# RelayDriver.net
KiCad netlist of a schematic drawn in Altium Designer
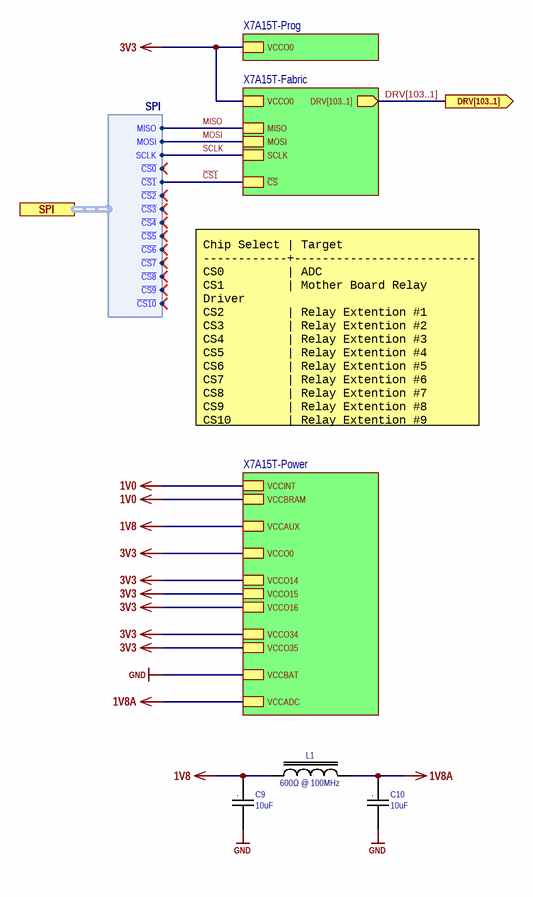
[diagram p0: RelayDriver.SchDoc]

(export (version "E")
  (design (tool "Eeschema 10.0.6"))
  (components
    (comp (ref "C9")
      (value "10uF")
      (footprint "C0805 Reflow")
      (description "CAP CER 10UF 10V X7R 0805")
      (fields
        (field (name "TOLERANCE") "±10%")
        (field (name "02. DISTRIBUTOR PART NUMBER") "1276-1764-6-ND")
        (field (name "13. CREATED DATE/NAME") "AUG2018/Hören")
      )
      (libsource (lib "chickenfood") (part "C"))
    )
    (comp (ref "C10")
      (value "10uF")
      (footprint "C0805 Reflow")
      (description "CAP CER 10UF 10V X7R 0805")
      (fields
        (field (name "TOLERANCE") "±10%")
        (field (name "02. DISTRIBUTOR PART NUMBER") "1276-1764-6-ND")
        (field (name "13. CREATED DATE/NAME") "AUG2018/Hören")
      )
      (libsource (lib "chickenfood") (part "C"))
    )
    (comp (ref "L1")
      (value "L")
      (footprint "FB0805")
      (description "FERRITE BEAD 600 OHM 0805 1LN")
      (fields
        (field (name "NOMINAL IMPEDANCE") "600Ω @ 100MHz")
        (field (name "02. DISTRIBUTOR PART NUMBER") "732-1620-6-ND")
        (field (name "07. MANUFACTURER  PART NUMBER") "742792040")
        (field (name "13. CREATED DATE/NAME") "AUG2018/Hören")
      )
      (libsource (lib "chickenfood") (part "FB"))
    )
  )
  (nets
    (net (code "112") (name "1V8") (class "Default")
      (node (ref "C9") (pin "1") (pinfunction "1_1") (pintype "passive"))
      (node (ref "L1") (pin "1") (pinfunction "1_1") (pintype "passive"))
    )
    (net (code "113") (name "1V8A") (class "Default")
      (node (ref "C10") (pin "1") (pinfunction "1_1") (pintype "passive"))
      (node (ref "L1") (pin "2") (pinfunction "2_2") (pintype "passive"))
    )
    (net (code "115") (name "GND") (class "Default")
      (node (ref "C10") (pin "2") (pinfunction "2_2") (pintype "passive"))
      (node (ref "C9") (pin "2") (pinfunction "2_2") (pintype "passive"))
    )
  )
)
